# multiple_tile.net
KiCad netlist of a schematic drawn in EAGLE
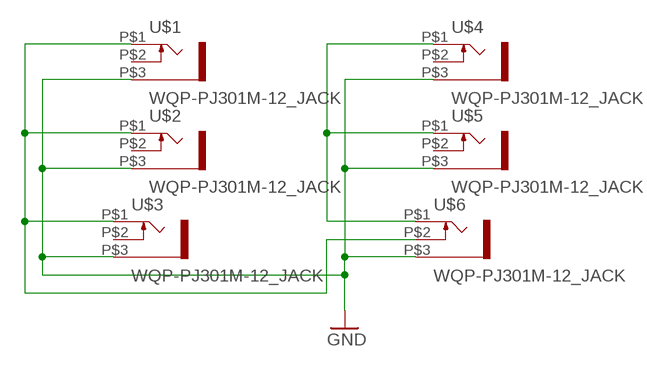
[diagram p0: schematic, sheet 1]

(export (version "E")
  (design (tool "Eeschema 10.0.6"))
  (components
    (comp (ref "U$1")
      (value "WQP-PJ301M-12_JACK")
      (footprint "eagle-import:WQP-PJ301M-12_JACK")
      (libsource (lib "eagle-import") (part "WQP-PJ301M-12_JACK"))
    )
    (comp (ref "U$2")
      (value "WQP-PJ301M-12_JACK")
      (footprint "eagle-import:WQP-PJ301M-12_JACK")
      (libsource (lib "eagle-import") (part "WQP-PJ301M-12_JACK"))
    )
    (comp (ref "U$3")
      (value "WQP-PJ301M-12_JACK")
      (footprint "eagle-import:WQP-PJ301M-12_JACK")
      (libsource (lib "eagle-import") (part "WQP-PJ301M-12_JACK"))
    )
    (comp (ref "U$4")
      (value "WQP-PJ301M-12_JACK")
      (footprint "eagle-import:WQP-PJ301M-12_JACK")
      (libsource (lib "eagle-import") (part "WQP-PJ301M-12_JACK"))
    )
    (comp (ref "U$5")
      (value "WQP-PJ301M-12_JACK")
      (footprint "eagle-import:WQP-PJ301M-12_JACK")
      (libsource (lib "eagle-import") (part "WQP-PJ301M-12_JACK"))
    )
    (comp (ref "U$6")
      (value "WQP-PJ301M-12_JACK")
      (footprint "eagle-import:WQP-PJ301M-12_JACK")
      (libsource (lib "eagle-import") (part "WQP-PJ301M-12_JACK"))
    )
  )
  (nets
    (net (code "1") (name "GND") (class "Default")
      (node (ref "U$1") (pin "P$3") (pinfunction "1_P$3") (pintype "passive"))
      (node (ref "U$2") (pin "P$3") (pinfunction "1_P$3") (pintype "passive"))
      (node (ref "U$3") (pin "P$3") (pinfunction "1_P$3") (pintype "passive"))
      (node (ref "U$4") (pin "P$3") (pinfunction "1_P$3") (pintype "passive"))
      (node (ref "U$5") (pin "P$3") (pinfunction "1_P$3") (pintype "passive"))
      (node (ref "U$6") (pin "P$3") (pinfunction "1_P$3") (pintype "passive"))
    )
    (net (code "2") (name "Net-(U$1-2)") (class "Default")
      (node (ref "U$1") (pin "P$1") (pinfunction "2_P$1") (pintype "passive"))
      (node (ref "U$2") (pin "P$1") (pinfunction "2_P$1") (pintype "passive"))
      (node (ref "U$3") (pin "P$1") (pinfunction "2_P$1") (pintype "passive"))
      (node (ref "U$6") (pin "P$2") (pinfunction "3_P$2") (pintype "passive"))
    )
    (net (code "3") (name "Net-(U$4-2)") (class "Default")
      (node (ref "U$4") (pin "P$1") (pinfunction "2_P$1") (pintype "passive"))
      (node (ref "U$5") (pin "P$1") (pinfunction "2_P$1") (pintype "passive"))
      (node (ref "U$6") (pin "P$1") (pinfunction "2_P$1") (pintype "passive"))
    )
    (net (code "4") (name "unconnected-(U$1-3-PadP$2)") (class "Default")
      (node (ref "U$1") (pin "P$2") (pinfunction "3_P$2") (pintype "passive"))
    )
    (net (code "5") (name "unconnected-(U$2-3-PadP$2)") (class "Default")
      (node (ref "U$2") (pin "P$2") (pinfunction "3_P$2") (pintype "passive"))
    )
    (net (code "6") (name "unconnected-(U$3-3-PadP$2)") (class "Default")
      (node (ref "U$3") (pin "P$2") (pinfunction "3_P$2") (pintype "passive"))
    )
    (net (code "7") (name "unconnected-(U$4-3-PadP$2)") (class "Default")
      (node (ref "U$4") (pin "P$2") (pinfunction "3_P$2") (pintype "passive"))
    )
    (net (code "8") (name "unconnected-(U$5-3-PadP$2)") (class "Default")
      (node (ref "U$5") (pin "P$2") (pinfunction "3_P$2") (pintype "passive"))
    )
  )
)
